# sim_ckt.net
KiCad netlist of a schematic drawn in Altium Designer
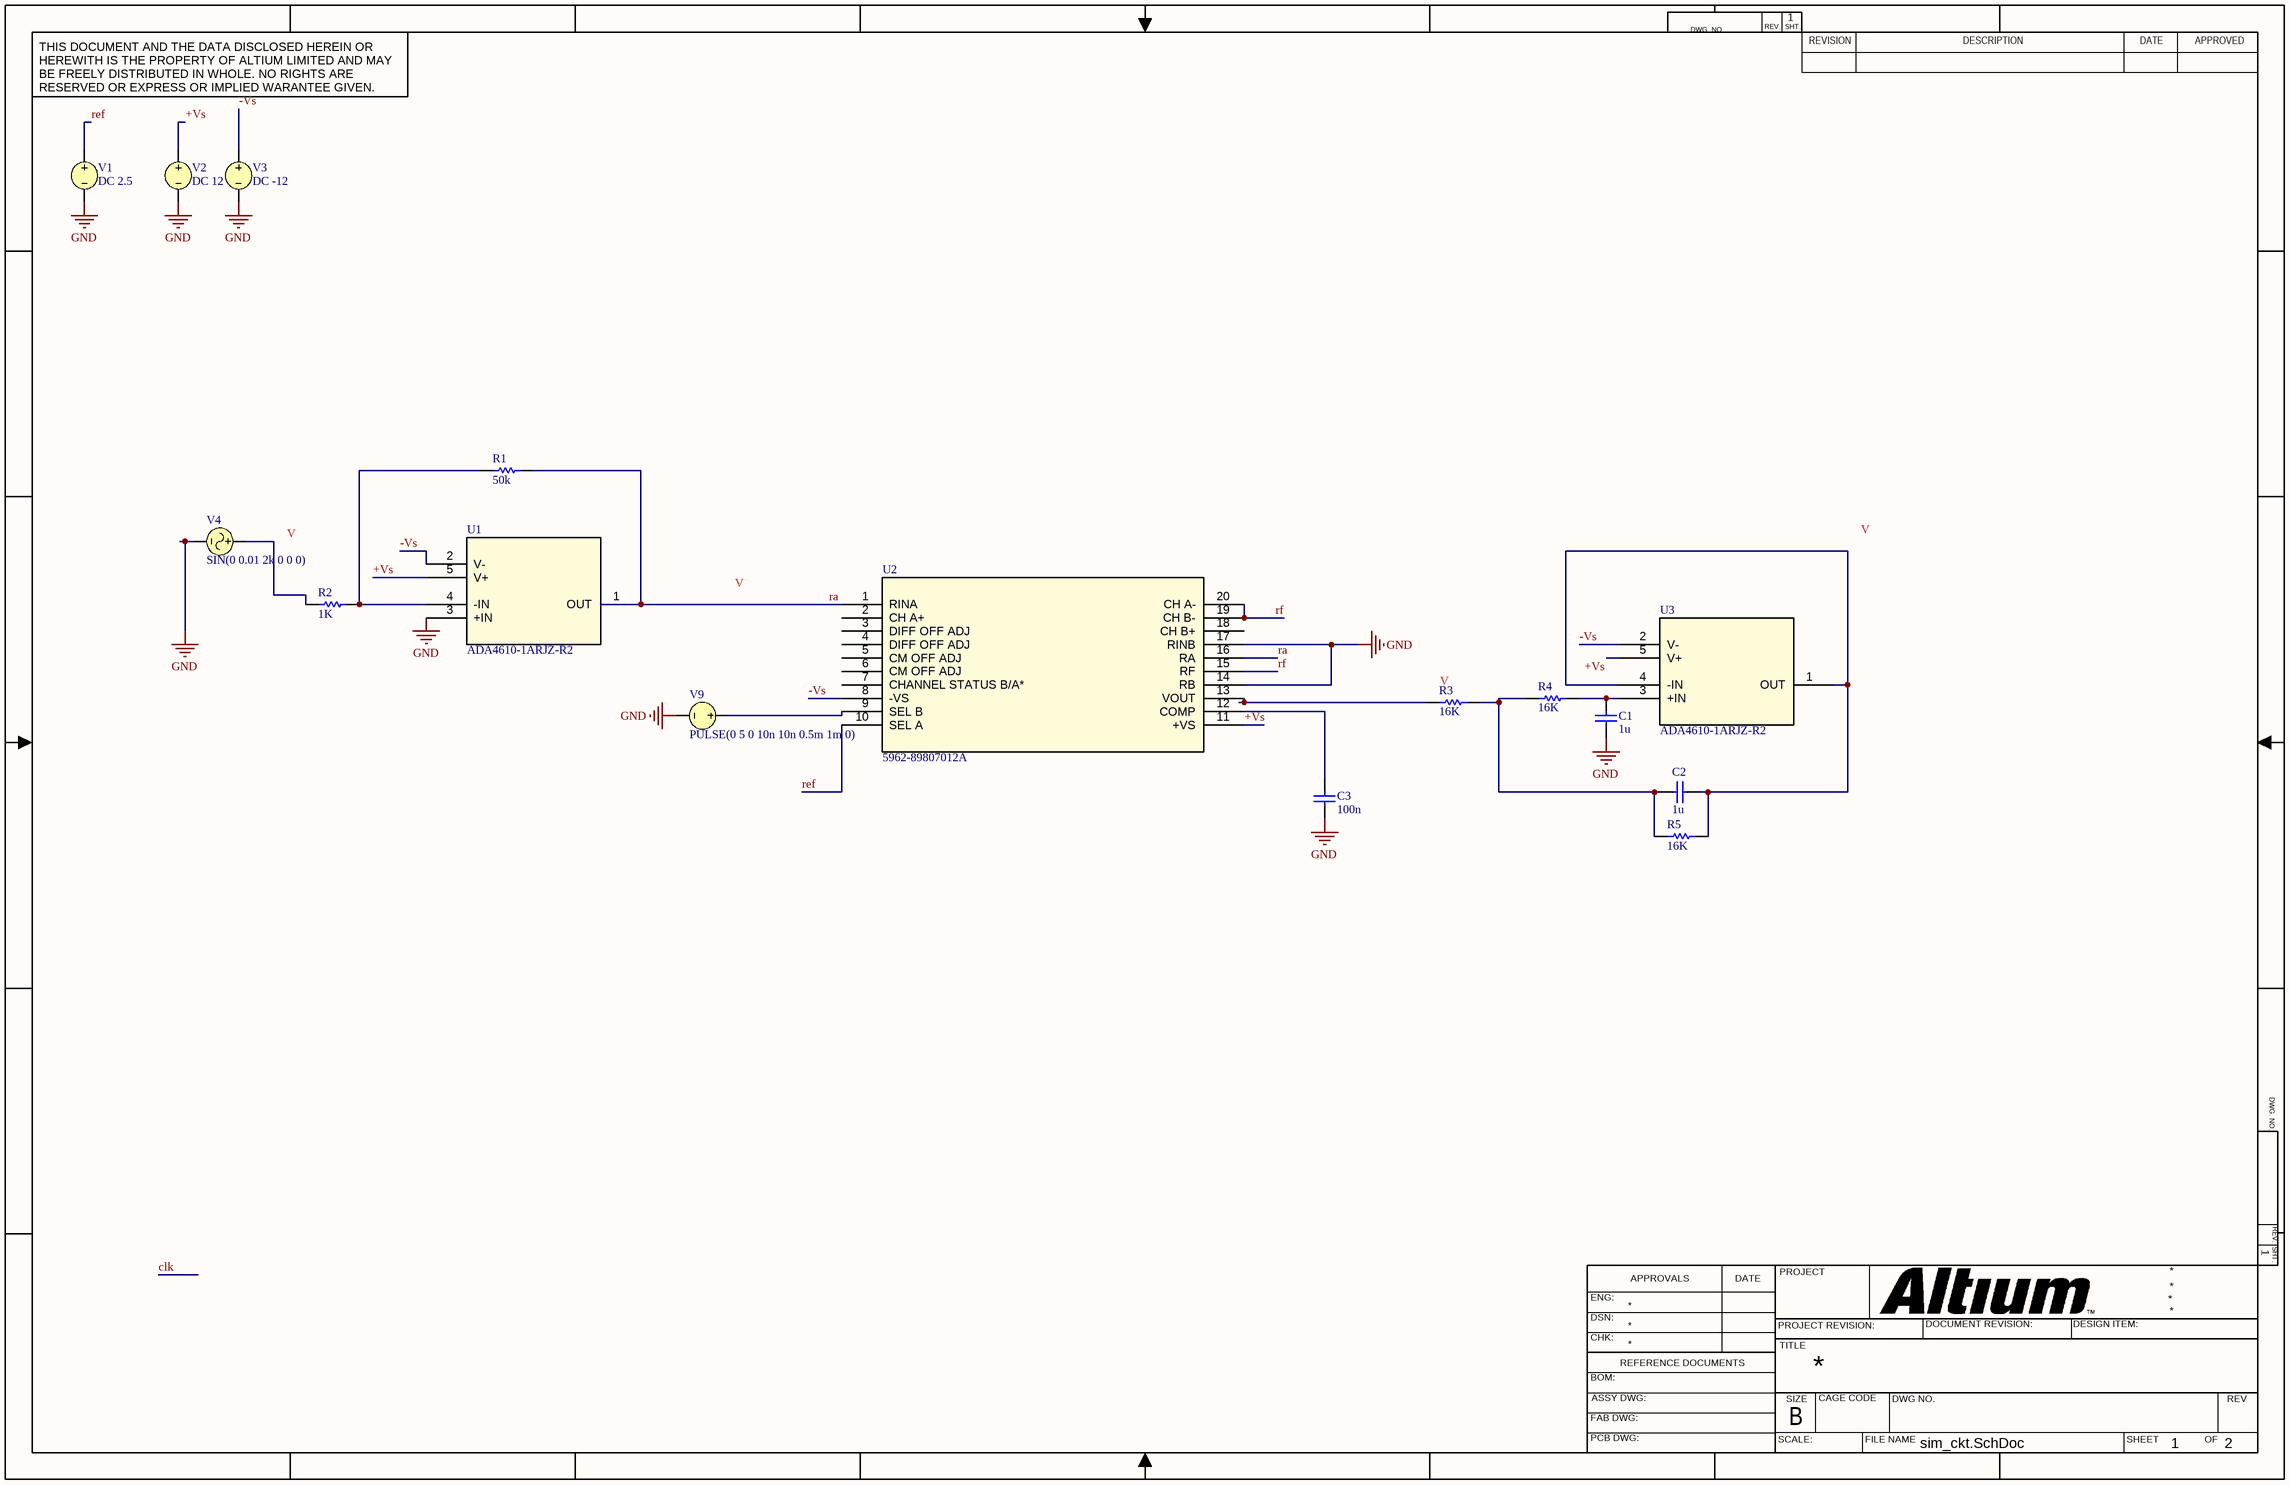
[diagram p0: sim_ckt.SchDoc]

(export (version "E")
  (design (tool "Eeschema 10.0.6"))
  (components
    (comp (ref "C1")
      (value "1u")
      (description "Capacitor")
      (libsource (lib "Simulation Generic Components") (part "Capacitor"))
    )
    (comp (ref "C2")
      (value "1u")
      (description "Capacitor")
      (libsource (lib "Simulation Generic Components") (part "Capacitor"))
    )
    (comp (ref "C3")
      (value "100n")
      (description "Capacitor")
      (libsource (lib "Simulation Generic Components") (part "Capacitor"))
    )
    (comp (ref "R1")
      (value "50k")
      (description "Resistor")
      (libsource (lib "Simulation Generic Components") (part "Resistor"))
    )
    (comp (ref "R2")
      (value "1K")
      (description "Resistor")
      (libsource (lib "Simulation Generic Components") (part "Resistor"))
    )
    (comp (ref "R3")
      (value "16K")
      (description "Resistor")
      (libsource (lib "Simulation Generic Components") (part "Resistor"))
    )
    (comp (ref "R4")
      (value "16K")
      (description "Resistor")
      (libsource (lib "Simulation Generic Components") (part "Resistor"))
    )
    (comp (ref "R5")
      (value "16K")
      (description "Resistor")
      (libsource (lib "Simulation Generic Components") (part "Resistor"))
    )
    (comp (ref "U1")
      (value "ADA4610-1ARJZ-R2")
      (footprint "RJ_5_ADI")
      (description "Low Noise, Precision, Rail-to-Rail Output, JFET Single Op Amp")
      (fields (field (name "COPYRIGHT") "Copyright (C) 2026 Ultra Librarian. All rights reserved."))
      (libsource (lib "ADA4610-1ARJZ-R2") (part "ADA4610-1ARJZ-R2"))
    )
    (comp (ref "U2")
      (value "5962-89807012A")
      (footprint "E_20_1_ADI")
      (description "Balanced Modulator/Demodulator")
      (fields (field (name "COPYRIGHT") "Copyright (C) 2026 Ultra Librarian. All rights reserved."))
      (libsource (lib "5962-89807012A") (part "5962-89807012A"))
    )
    (comp (ref "U3")
      (value "ADA4610-1ARJZ-R2")
      (footprint "RJ_5_ADI")
      (description "Low Noise, Precision, Rail-to-Rail Output, JFET Single Op Amp")
      (fields (field (name "COPYRIGHT") "Copyright (C) 2026 Ultra Librarian. All rights reserved."))
      (libsource (lib "ADA4610-1ARJZ-R2") (part "ADA4610-1ARJZ-R2"))
    )
    (comp (ref "V1")
      (value "DC 2.5")
      (description "Voltage Source")
      (fields (field (name "PUBLISHER") "Altium Limited"))
      (libsource (lib "Simulation Generic Components") (part "VSRC"))
    )
    (comp (ref "V2")
      (value "DC 12")
      (description "Voltage Source")
      (fields (field (name "PUBLISHER") "Altium Limited"))
      (libsource (lib "Simulation Generic Components") (part "VSRC"))
    )
    (comp (ref "V3")
      (value "DC -12")
      (description "Voltage Source")
      (fields (field (name "PUBLISHER") "Altium Limited"))
      (libsource (lib "Simulation Generic Components") (part "VSRC"))
    )
    (comp (ref "V4")
      (value "SIN(0 0.01 2k 0 0 0)")
      (description "Sinusoidal Voltage Source")
      (fields (field (name "PUBLISHER") "Altium Limited"))
      (libsource (lib "Simulation Generic Components") (part "VSIN"))
    )
    (comp (ref "V9")
      (value "PULSE(0 5 0 10n 10n 0.5m 1m 0)")
      (description "Voltage Source")
      (fields (field (name "PUBLISHER") "Altium Limited"))
      (libsource (lib "Simulation Generic Components") (part "VSRC"))
    )
  )
  (nets
    (net (code "1") (name "/+Vs") (class "Default")
      (node (ref "U1") (pin "5") (pinfunction "V+_5") (pintype "passive"))
      (node (ref "U2") (pin "11") (pinfunction "+VS_11") (pintype "power_in"))
      (node (ref "U3") (pin "5") (pinfunction "V+_5") (pintype "passive"))
      (node (ref "V2") (pin "1") (pinfunction "1_1") (pintype "passive"))
    )
    (net (code "2") (name "/-Vs") (class "Default")
      (node (ref "U1") (pin "2") (pinfunction "V-_2") (pintype "passive"))
      (node (ref "U2") (pin "8") (pinfunction "-VS_8") (pintype "power_in"))
      (node (ref "U3") (pin "2") (pinfunction "V-_2") (pintype "passive"))
      (node (ref "V3") (pin "1") (pinfunction "1_1") (pintype "passive"))
    )
    (net (code "4") (name "/ra") (class "Default")
      (node (ref "R1") (pin "2") (pinfunction "2_2") (pintype "passive"))
      (node (ref "U1") (pin "1") (pinfunction "OUT_1") (pintype "passive"))
      (node (ref "U2") (pin "1") (pinfunction "RINA_1") (pintype "passive"))
      (node (ref "U2") (pin "16") (pinfunction "RA_16") (pintype "passive"))
    )
    (net (code "5") (name "/ref") (class "Default")
      (node (ref "U2") (pin "10") (pinfunction "SEL_A_10") (pintype "passive"))
      (node (ref "V1") (pin "1") (pinfunction "1_1") (pintype "passive"))
    )
    (net (code "6") (name "/rf") (class "Default")
      (node (ref "U2") (pin "15") (pinfunction "RF_15") (pintype "passive"))
      (node (ref "U2") (pin "19") (pinfunction "CH_B-_19") (pintype "passive"))
      (node (ref "U2") (pin "20") (pinfunction "CH_A-_20") (pintype "passive"))
    )
    (net (code "7") (name "GND") (class "Default")
      (node (ref "C1") (pin "1") (pinfunction "1_1") (pintype "passive"))
      (node (ref "C3") (pin "2") (pinfunction "2_2") (pintype "passive"))
      (node (ref "U1") (pin "3") (pinfunction "+IN_3") (pintype "passive"))
      (node (ref "U2") (pin "14") (pinfunction "RB_14") (pintype "passive"))
      (node (ref "U2") (pin "17") (pinfunction "RINB_17") (pintype "passive"))
      (node (ref "V1") (pin "2") (pinfunction "2_2") (pintype "passive"))
      (node (ref "V2") (pin "2") (pinfunction "2_2") (pintype "passive"))
      (node (ref "V3") (pin "2") (pinfunction "2_2") (pintype "passive"))
      (node (ref "V4") (pin "2") (pinfunction "2_2") (pintype "passive"))
      (node (ref "V9") (pin "2") (pinfunction "2_2") (pintype "passive"))
    )
    (net (code "8") (name "Net-(C2-Pad1)") (class "Default")
      (node (ref "C2") (pin "1") (pinfunction "1_1") (pintype "passive"))
      (node (ref "R3") (pin "2") (pinfunction "2_2") (pintype "passive"))
      (node (ref "R4") (pin "1") (pinfunction "1_1") (pintype "passive"))
      (node (ref "R5") (pin "1") (pinfunction "1_1") (pintype "passive"))
    )
    (net (code "9") (name "Net-(R2-Pad1)") (class "Default")
      (node (ref "R2") (pin "1") (pinfunction "1_1") (pintype "passive"))
      (node (ref "V4") (pin "1") (pinfunction "1_1") (pintype "passive"))
    )
    (net (code "10") (name "Net-(U1--IN)") (class "Default")
      (node (ref "R1") (pin "1") (pinfunction "1_1") (pintype "passive"))
      (node (ref "R2") (pin "2") (pinfunction "2_2") (pintype "passive"))
      (node (ref "U1") (pin "4") (pinfunction "-IN_4") (pintype "passive"))
    )
    (net (code "11") (name "Net-(U2-COMP)") (class "Default")
      (node (ref "C3") (pin "1") (pinfunction "1_1") (pintype "passive"))
      (node (ref "U2") (pin "12") (pinfunction "COMP_12") (pintype "passive"))
    )
    (net (code "12") (name "Net-(U2-SEL_B)") (class "Default")
      (node (ref "U2") (pin "9") (pinfunction "SEL_B_9") (pintype "passive"))
      (node (ref "V9") (pin "1") (pinfunction "1_1") (pintype "passive"))
    )
    (net (code "13") (name "Net-(U2-VOUT)") (class "Default")
      (node (ref "R3") (pin "1") (pinfunction "1_1") (pintype "passive"))
      (node (ref "U2") (pin "13") (pinfunction "VOUT_13") (pintype "passive"))
    )
    (net (code "14") (name "Net-(U3-+IN)") (class "Default")
      (node (ref "C1") (pin "2") (pinfunction "2_2") (pintype "passive"))
      (node (ref "R4") (pin "2") (pinfunction "2_2") (pintype "passive"))
      (node (ref "U3") (pin "3") (pinfunction "+IN_3") (pintype "passive"))
    )
    (net (code "15") (name "Net-(U3--IN)") (class "Default")
      (node (ref "C2") (pin "2") (pinfunction "2_2") (pintype "passive"))
      (node (ref "R5") (pin "2") (pinfunction "2_2") (pintype "passive"))
      (node (ref "U3") (pin "1") (pinfunction "OUT_1") (pintype "passive"))
      (node (ref "U3") (pin "4") (pinfunction "-IN_4") (pintype "passive"))
    )
    (net (code "16") (name "unconnected-(U2-CHANNEL_STATUS_B{slash}A*-Pad7)") (class "Default")
      (node (ref "U2") (pin "7") (pinfunction "CHANNEL_STATUS_B/A*_7") (pintype "passive"))
    )
    (net (code "17") (name "unconnected-(U2-CH_A+-Pad2)") (class "Default")
      (node (ref "U2") (pin "2") (pinfunction "CH_A+_2") (pintype "passive"))
    )
    (net (code "18") (name "unconnected-(U2-CH_B+-Pad18)") (class "Default")
      (node (ref "U2") (pin "18") (pinfunction "CH_B+_18") (pintype "passive"))
    )
    (net (code "19") (name "unconnected-(U2-CM_OFF_ADJ-Pad5)") (class "Default")
      (node (ref "U2") (pin "5") (pinfunction "CM_OFF_ADJ_5") (pintype "passive"))
    )
    (net (code "20") (name "unconnected-(U2-CM_OFF_ADJ-Pad6)") (class "Default")
      (node (ref "U2") (pin "6") (pinfunction "CM_OFF_ADJ_6") (pintype "passive"))
    )
    (net (code "21") (name "unconnected-(U2-DIFF_OFF_ADJ-Pad3)") (class "Default")
      (node (ref "U2") (pin "3") (pinfunction "DIFF_OFF_ADJ_3") (pintype "passive"))
    )
    (net (code "22") (name "unconnected-(U2-DIFF_OFF_ADJ-Pad4)") (class "Default")
      (node (ref "U2") (pin "4") (pinfunction "DIFF_OFF_ADJ_4") (pintype "passive"))
    )
  )
)
